# 2_-INTERFACE_CONNS.net
KiCad netlist of a schematic drawn in Altium Designer
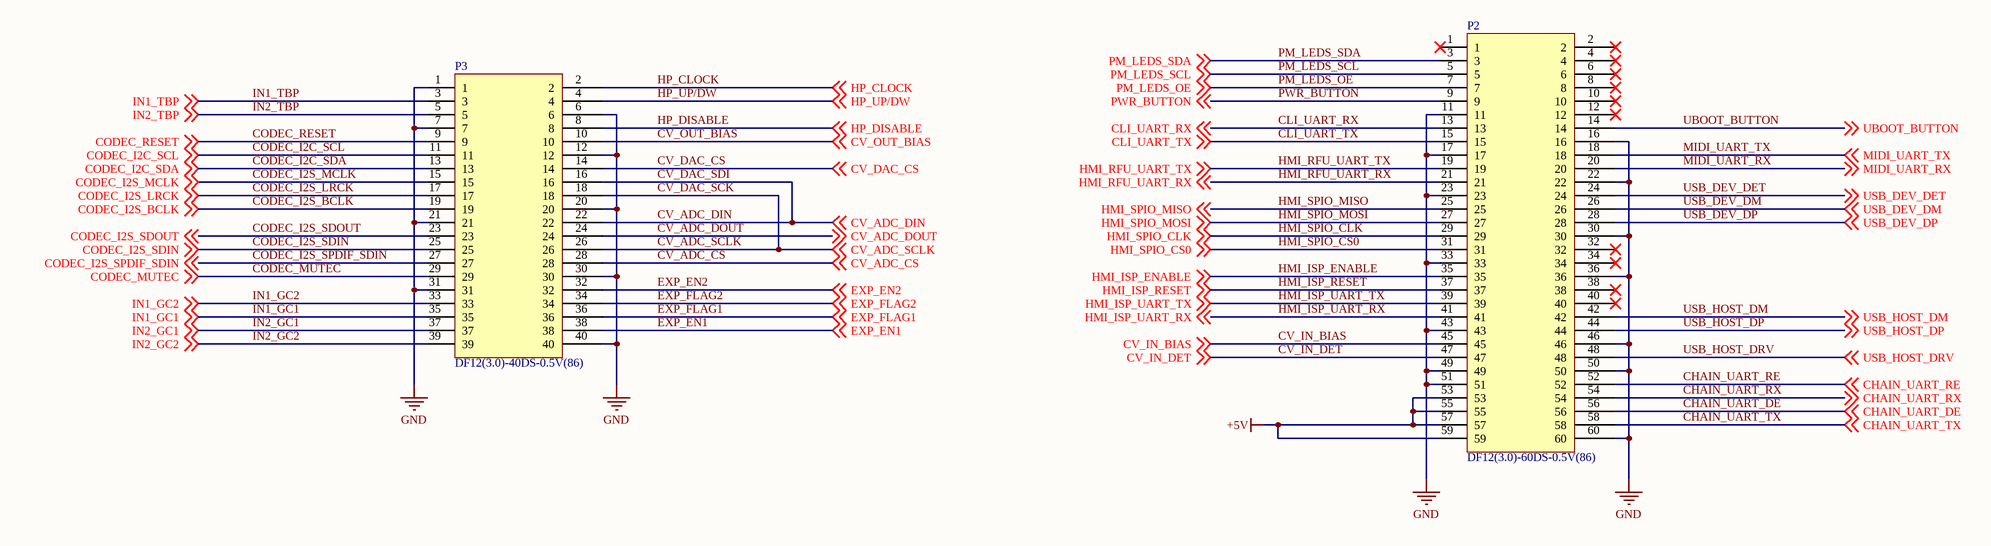
[diagram p0: [2]-INTERFACE_CONNS.SchDoc]

(export (version "E")
  (design (tool "Eeschema 10.0.6"))
  (components
    (comp (ref "P2")
      (value "DF12(3.0)-60DS-0.5V(86)")
      (footprint "DF12-60")
      (description "CONN RECEPT 60POS 3MM SMD 0.5MM")
      (libsource (lib "bitsnio") (part "DF12(3.0)-60DS-0.5V(86)"))
    )
    (comp (ref "P3")
      (value "DF12(3.0)-40DS-0.5V(86)")
      (footprint "DF12-40")
      (description "CONN RECEPT 40POS 3MM SMD 0.5MM")
      (libsource (lib "bitsnio") (part "DF12(3.0)-40DS-0.5V(86)"))
    )
  )
  (nets
    (net (code "1") (name "+5V") (class "Default")
      (node (ref "P2") (pin "53") (pinfunction "53_53") (pintype "passive"))
      (node (ref "P2") (pin "55") (pinfunction "55_55") (pintype "passive"))
      (node (ref "P2") (pin "57") (pinfunction "57_57") (pintype "passive"))
      (node (ref "P2") (pin "59") (pinfunction "59_59") (pintype "passive"))
    )
    (net (code "2") (name "CHAIN_UART_DE") (class "Default")
      (node (ref "P2") (pin "56") (pinfunction "56_56") (pintype "passive"))
    )
    (net (code "3") (name "CHAIN_UART_RE") (class "Default")
      (node (ref "P2") (pin "52") (pinfunction "52_52") (pintype "passive"))
    )
    (net (code "4") (name "CHAIN_UART_RX") (class "Default")
      (node (ref "P2") (pin "54") (pinfunction "54_54") (pintype "passive"))
    )
    (net (code "5") (name "CHAIN_UART_TX") (class "Default")
      (node (ref "P2") (pin "58") (pinfunction "58_58") (pintype "passive"))
    )
    (net (code "6") (name "CLI_UART_RX") (class "Default")
      (node (ref "P2") (pin "13") (pinfunction "13_13") (pintype "passive"))
    )
    (net (code "7") (name "CLI_UART_TX") (class "Default")
      (node (ref "P2") (pin "15") (pinfunction "15_15") (pintype "passive"))
    )
    (net (code "8") (name "CODEC_I2C_SCL") (class "Default")
      (node (ref "P3") (pin "11") (pinfunction "11_11") (pintype "passive"))
    )
    (net (code "9") (name "CODEC_I2C_SDA") (class "Default")
      (node (ref "P3") (pin "13") (pinfunction "13_13") (pintype "passive"))
    )
    (net (code "10") (name "CODEC_I2S_BCLK") (class "Default")
      (node (ref "P3") (pin "19") (pinfunction "19_19") (pintype "passive"))
    )
    (net (code "11") (name "CODEC_I2S_LRCK") (class "Default")
      (node (ref "P3") (pin "17") (pinfunction "17_17") (pintype "passive"))
    )
    (net (code "12") (name "CODEC_I2S_MCLK") (class "Default")
      (node (ref "P3") (pin "15") (pinfunction "15_15") (pintype "passive"))
    )
    (net (code "13") (name "CODEC_I2S_SDIN") (class "Default")
      (node (ref "P3") (pin "25") (pinfunction "25_25") (pintype "passive"))
    )
    (net (code "14") (name "CODEC_I2S_SDOUT") (class "Default")
      (node (ref "P3") (pin "23") (pinfunction "23_23") (pintype "passive"))
    )
    (net (code "15") (name "CODEC_I2S_SPDIF_SDIN") (class "Default")
      (node (ref "P3") (pin "27") (pinfunction "27_27") (pintype "passive"))
    )
    (net (code "16") (name "CODEC_MUTEC") (class "Default")
      (node (ref "P3") (pin "29") (pinfunction "29_29") (pintype "passive"))
    )
    (net (code "17") (name "CODEC_RESET") (class "Default")
      (node (ref "P3") (pin "9") (pinfunction "9_9") (pintype "passive"))
    )
    (net (code "18") (name "CV_ADC_CS") (class "Default")
      (node (ref "P3") (pin "28") (pinfunction "28_28") (pintype "passive"))
    )
    (net (code "19") (name "CV_ADC_DIN") (class "Default")
      (node (ref "P3") (pin "16") (pinfunction "16_16") (pintype "passive"))
      (node (ref "P3") (pin "22") (pinfunction "22_22") (pintype "passive"))
    )
    (net (code "20") (name "CV_ADC_DOUT") (class "Default")
      (node (ref "P3") (pin "24") (pinfunction "24_24") (pintype "passive"))
    )
    (net (code "21") (name "CV_ADC_SCLK") (class "Default")
      (node (ref "P3") (pin "18") (pinfunction "18_18") (pintype "passive"))
      (node (ref "P3") (pin "26") (pinfunction "26_26") (pintype "passive"))
    )
    (net (code "22") (name "CV_DAC_CS") (class "Default")
      (node (ref "P3") (pin "14") (pinfunction "14_14") (pintype "passive"))
    )
    (net (code "23") (name "CV_IN_BIAS") (class "Default")
      (node (ref "P2") (pin "45") (pinfunction "45_45") (pintype "passive"))
    )
    (net (code "24") (name "CV_IN_DET") (class "Default")
      (node (ref "P2") (pin "47") (pinfunction "47_47") (pintype "passive"))
    )
    (net (code "25") (name "CV_OUT_BIAS") (class "Default")
      (node (ref "P3") (pin "10") (pinfunction "10_10") (pintype "passive"))
    )
    (net (code "26") (name "EXP_EN1") (class "Default")
      (node (ref "P3") (pin "38") (pinfunction "38_38") (pintype "passive"))
    )
    (net (code "27") (name "EXP_EN2") (class "Default")
      (node (ref "P3") (pin "32") (pinfunction "32_32") (pintype "passive"))
    )
    (net (code "28") (name "EXP_FLAG1") (class "Default")
      (node (ref "P3") (pin "36") (pinfunction "36_36") (pintype "passive"))
    )
    (net (code "29") (name "EXP_FLAG2") (class "Default")
      (node (ref "P3") (pin "34") (pinfunction "34_34") (pintype "passive"))
    )
    (net (code "30") (name "GND") (class "Default")
      (node (ref "P2") (pin "11") (pinfunction "11_11") (pintype "passive"))
      (node (ref "P2") (pin "16") (pinfunction "16_16") (pintype "passive"))
      (node (ref "P2") (pin "17") (pinfunction "17_17") (pintype "passive"))
      (node (ref "P2") (pin "22") (pinfunction "22_22") (pintype "passive"))
      (node (ref "P2") (pin "23") (pinfunction "23_23") (pintype "passive"))
      (node (ref "P2") (pin "30") (pinfunction "30_30") (pintype "passive"))
      (node (ref "P2") (pin "33") (pinfunction "33_33") (pintype "passive"))
      (node (ref "P2") (pin "36") (pinfunction "36_36") (pintype "passive"))
      (node (ref "P2") (pin "43") (pinfunction "43_43") (pintype "passive"))
      (node (ref "P2") (pin "46") (pinfunction "46_46") (pintype "passive"))
      (node (ref "P2") (pin "49") (pinfunction "49_49") (pintype "passive"))
      (node (ref "P2") (pin "50") (pinfunction "50_50") (pintype "passive"))
      (node (ref "P2") (pin "51") (pinfunction "51_51") (pintype "passive"))
      (node (ref "P2") (pin "60") (pinfunction "60_60") (pintype "passive"))
      (node (ref "P3") (pin "1") (pinfunction "1_1") (pintype "passive"))
      (node (ref "P3") (pin "12") (pinfunction "12_12") (pintype "passive"))
      (node (ref "P3") (pin "20") (pinfunction "20_20") (pintype "passive"))
      (node (ref "P3") (pin "21") (pinfunction "21_21") (pintype "passive"))
      (node (ref "P3") (pin "30") (pinfunction "30_30") (pintype "passive"))
      (node (ref "P3") (pin "31") (pinfunction "31_31") (pintype "passive"))
      (node (ref "P3") (pin "40") (pinfunction "40_40") (pintype "passive"))
      (node (ref "P3") (pin "6") (pinfunction "6_6") (pintype "passive"))
      (node (ref "P3") (pin "7") (pinfunction "7_7") (pintype "passive"))
    )
    (net (code "31") (name "HMI_ISP_ENABLE") (class "Default")
      (node (ref "P2") (pin "35") (pinfunction "35_35") (pintype "passive"))
    )
    (net (code "32") (name "HMI_ISP_RESET") (class "Default")
      (node (ref "P2") (pin "37") (pinfunction "37_37") (pintype "passive"))
    )
    (net (code "33") (name "HMI_ISP_UART_RX") (class "Default")
      (node (ref "P2") (pin "41") (pinfunction "41_41") (pintype "passive"))
    )
    (net (code "34") (name "HMI_ISP_UART_TX") (class "Default")
      (node (ref "P2") (pin "39") (pinfunction "39_39") (pintype "passive"))
    )
    (net (code "35") (name "HMI_RFU_UART_RX") (class "Default")
      (node (ref "P2") (pin "21") (pinfunction "21_21") (pintype "passive"))
    )
    (net (code "36") (name "HMI_RFU_UART_TX") (class "Default")
      (node (ref "P2") (pin "19") (pinfunction "19_19") (pintype "passive"))
    )
    (net (code "37") (name "HMI_SPIO_CLK") (class "Default")
      (node (ref "P2") (pin "29") (pinfunction "29_29") (pintype "passive"))
    )
    (net (code "38") (name "HMI_SPIO_CS0") (class "Default")
      (node (ref "P2") (pin "31") (pinfunction "31_31") (pintype "passive"))
    )
    (net (code "39") (name "HMI_SPIO_MISO") (class "Default")
      (node (ref "P2") (pin "25") (pinfunction "25_25") (pintype "passive"))
    )
    (net (code "40") (name "HMI_SPIO_MOSI") (class "Default")
      (node (ref "P2") (pin "27") (pinfunction "27_27") (pintype "passive"))
    )
    (net (code "41") (name "HP_CLOCK") (class "Default")
      (node (ref "P3") (pin "2") (pinfunction "2_2") (pintype "passive"))
    )
    (net (code "42") (name "HP_DISABLE") (class "Default")
      (node (ref "P3") (pin "8") (pinfunction "8_8") (pintype "passive"))
    )
    (net (code "43") (name "HP_UP{slash}DW") (class "Default")
      (node (ref "P3") (pin "4") (pinfunction "4_4") (pintype "passive"))
    )
    (net (code "44") (name "IN1_GC1") (class "Default")
      (node (ref "P3") (pin "35") (pinfunction "35_35") (pintype "passive"))
    )
    (net (code "45") (name "IN1_GC2") (class "Default")
      (node (ref "P3") (pin "33") (pinfunction "33_33") (pintype "passive"))
    )
    (net (code "46") (name "IN1_TBP") (class "Default")
      (node (ref "P3") (pin "3") (pinfunction "3_3") (pintype "passive"))
    )
    (net (code "47") (name "IN2_GC1") (class "Default")
      (node (ref "P3") (pin "37") (pinfunction "37_37") (pintype "passive"))
    )
    (net (code "48") (name "IN2_GC2") (class "Default")
      (node (ref "P3") (pin "39") (pinfunction "39_39") (pintype "passive"))
    )
    (net (code "49") (name "IN2_TBP") (class "Default")
      (node (ref "P3") (pin "5") (pinfunction "5_5") (pintype "passive"))
    )
    (net (code "50") (name "MIDI_UART_RX") (class "Default")
      (node (ref "P2") (pin "20") (pinfunction "20_20") (pintype "passive"))
    )
    (net (code "51") (name "MIDI_UART_TX") (class "Default")
      (node (ref "P2") (pin "18") (pinfunction "18_18") (pintype "passive"))
    )
    (net (code "52") (name "PM_LEDS_OE") (class "Default")
      (node (ref "P2") (pin "7") (pinfunction "7_7") (pintype "passive"))
    )
    (net (code "53") (name "PM_LEDS_SCL") (class "Default")
      (node (ref "P2") (pin "5") (pinfunction "5_5") (pintype "passive"))
    )
    (net (code "54") (name "PM_LEDS_SDA") (class "Default")
      (node (ref "P2") (pin "3") (pinfunction "3_3") (pintype "passive"))
    )
    (net (code "55") (name "PWR_BUTTON") (class "Default")
      (node (ref "P2") (pin "9") (pinfunction "9_9") (pintype "passive"))
    )
    (net (code "56") (name "UBOOT_BUTTON") (class "Default")
      (node (ref "P2") (pin "14") (pinfunction "14_14") (pintype "passive"))
    )
    (net (code "57") (name "USB_DEV_DET") (class "Default")
      (node (ref "P2") (pin "24") (pinfunction "24_24") (pintype "passive"))
    )
    (net (code "58") (name "USB_DEV_DM") (class "Default")
      (node (ref "P2") (pin "26") (pinfunction "26_26") (pintype "passive"))
    )
    (net (code "59") (name "USB_DEV_DP") (class "Default")
      (node (ref "P2") (pin "28") (pinfunction "28_28") (pintype "passive"))
    )
    (net (code "60") (name "USB_HOST_DM") (class "Default")
      (node (ref "P2") (pin "42") (pinfunction "42_42") (pintype "passive"))
    )
    (net (code "61") (name "USB_HOST_DP") (class "Default")
      (node (ref "P2") (pin "44") (pinfunction "44_44") (pintype "passive"))
    )
    (net (code "62") (name "USB_HOST_DRV") (class "Default")
      (node (ref "P2") (pin "48") (pinfunction "48_48") (pintype "passive"))
    )
    (net (code "63") (name "unconnected-(P2-Pad1)") (class "Default")
      (node (ref "P2") (pin "1") (pinfunction "1_1") (pintype "passive+no_connect"))
    )
    (net (code "64") (name "unconnected-(P2-Pad2)") (class "Default")
      (node (ref "P2") (pin "2") (pinfunction "2_2") (pintype "passive+no_connect"))
    )
    (net (code "65") (name "unconnected-(P2-Pad4)") (class "Default")
      (node (ref "P2") (pin "4") (pinfunction "4_4") (pintype "passive+no_connect"))
    )
    (net (code "66") (name "unconnected-(P2-Pad6)") (class "Default")
      (node (ref "P2") (pin "6") (pinfunction "6_6") (pintype "passive+no_connect"))
    )
    (net (code "67") (name "unconnected-(P2-Pad8)") (class "Default")
      (node (ref "P2") (pin "8") (pinfunction "8_8") (pintype "passive+no_connect"))
    )
    (net (code "68") (name "unconnected-(P2-Pad10)") (class "Default")
      (node (ref "P2") (pin "10") (pinfunction "10_10") (pintype "passive+no_connect"))
    )
    (net (code "69") (name "unconnected-(P2-Pad12)") (class "Default")
      (node (ref "P2") (pin "12") (pinfunction "12_12") (pintype "passive+no_connect"))
    )
    (net (code "70") (name "unconnected-(P2-Pad32)") (class "Default")
      (node (ref "P2") (pin "32") (pinfunction "32_32") (pintype "passive+no_connect"))
    )
    (net (code "71") (name "unconnected-(P2-Pad34)") (class "Default")
      (node (ref "P2") (pin "34") (pinfunction "34_34") (pintype "passive+no_connect"))
    )
    (net (code "72") (name "unconnected-(P2-Pad38)") (class "Default")
      (node (ref "P2") (pin "38") (pinfunction "38_38") (pintype "passive+no_connect"))
    )
    (net (code "73") (name "unconnected-(P2-Pad40)") (class "Default")
      (node (ref "P2") (pin "40") (pinfunction "40_40") (pintype "passive+no_connect"))
    )
  )
)
